# adc.net
KiCad netlist of a schematic drawn in Altium Designer
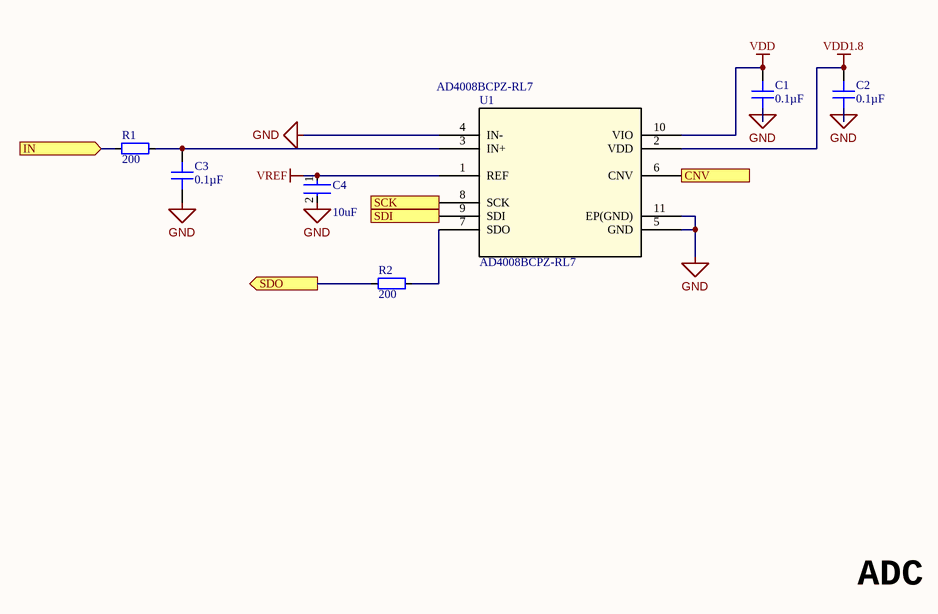
[diagram p0: adc.SchDoc]

(export (version "E")
  (design (tool "Eeschema 10.0.6"))
  (components
    (comp (ref "C1")
      (value "0.1µF")
      (footprint "FP-GRM155-0_05-IPC_B")
      (description "CAP CER 0.1UF 25V X7R 0402")
      (fields (field (name "MANUFACTURER") "AVX Corporation") (field (name "PART NUMBER") "04023C104KAT2A"))
      (libsource (lib "Celestial Altium Library - altium_library") (part "Capacitor"))
    )
    (comp (ref "C2")
      (value "0.1µF")
      (footprint "FP-GRM155-0_05-IPC_B")
      (description "CAP CER 0.1UF 25V X7R 0402")
      (fields (field (name "MANUFACTURER") "AVX Corporation") (field (name "PART NUMBER") "04023C104KAT2A"))
      (libsource (lib "Celestial Altium Library - altium_library") (part "Capacitor"))
    )
    (comp (ref "C3")
      (value "0.1µF")
      (footprint "FP-GRM155-0_05-IPC_B")
      (description "CAP CER 0.1UF 25V X7R 0402")
      (fields (field (name "MANUFACTURER") "AVX Corporation") (field (name "PART NUMBER") "04023C104KAT2A"))
      (libsource (lib "Celestial Altium Library - altium_library") (part "Capacitor"))
    )
    (comp (ref "C4")
      (value "CL21B106KQQNNNG")
      (footprint "FP-CL21-IPC_C")
      (description "CL21 Series 0805 10uF 6.3V ±10% Tolerance X7R Multilayer Ceramic Chip Capacitor")
      (fields
        (field (name "CAPACITANCE") "10uF")
        (field (name "TOLERANCE") "10%")
        (field (name "VOLTAGE") "6.3V")
      )
      (libsource (lib "Altium Content Vault") (part "b4654b650e69147ec39a6b967a45e02"))
    )
    (comp (ref "R1")
      (value "200")
      (footprint "FP-CRCW0402-e3-IPC_B")
      (description "Resistor")
      (fields (field (name "Comment") "Res_0402"))
      (libsource (lib "SCH_Passive") (part "Res_0402"))
    )
    (comp (ref "R2")
      (value "200")
      (footprint "FP-CRCW0402-e3-IPC_B")
      (description "Resistor")
      (fields (field (name "Comment") "Res_0402"))
      (libsource (lib "SCH_Passive") (part "Res_0402"))
    )
    (comp (ref "U1")
      (value "AD4008BCPZ-RL7")
      (footprint "CP_10_9")
      (description "16-Bit, 2 MSPS/1 MSPS/500 kSPS,\r\nPrecision, Pseudo Differential, SAR ADCs")
      (fields (field (name "SUPPLIER PART NUMBER 1") "AD4008BCPZ-RL7"))
      (libsource (lib "dvrk-s-pwm") (part "AD4008BCPZ-RL7"))
    )
  )
  (nets
    (net (code "1") (name "/CNV") (class "Default")
      (node (ref "U1") (pin "6") (pinfunction "CNV_6") (pintype "passive"))
    )
    (net (code "2") (name "/IN") (class "Default")
      (node (ref "R1") (pin "1") (pinfunction "1_1") (pintype "passive"))
    )
    (net (code "3") (name "/SCK") (class "Default")
      (node (ref "U1") (pin "8") (pinfunction "SCK_8") (pintype "passive"))
    )
    (net (code "4") (name "/SDI") (class "Default")
      (node (ref "U1") (pin "9") (pinfunction "SDI_9") (pintype "passive"))
    )
    (net (code "5") (name "/SDO") (class "Default")
      (node (ref "R2") (pin "1") (pinfunction "1_1") (pintype "passive"))
    )
    (net (code "6") (name "GND") (class "Default")
      (node (ref "C1") (pin "2") (pinfunction "2_2") (pintype "passive"))
      (node (ref "C2") (pin "2") (pinfunction "2_2") (pintype "passive"))
      (node (ref "C3") (pin "2") (pinfunction "2_2") (pintype "passive"))
      (node (ref "C4") (pin "2") (pinfunction "2_2") (pintype "passive"))
      (node (ref "U1") (pin "11") (pinfunction "EP(GND)_11") (pintype "passive"))
      (node (ref "U1") (pin "4") (pinfunction "IN-_4") (pintype "passive"))
      (node (ref "U1") (pin "5") (pinfunction "GND_5") (pintype "passive"))
    )
    (net (code "7") (name "Net-(U1-IN+)") (class "Default")
      (node (ref "C3") (pin "1") (pinfunction "1_1") (pintype "passive"))
      (node (ref "R1") (pin "2") (pinfunction "2_2") (pintype "passive"))
      (node (ref "U1") (pin "3") (pinfunction "IN+_3") (pintype "passive"))
    )
    (net (code "8") (name "Net-(U1-SDO)") (class "Default")
      (node (ref "R2") (pin "2") (pinfunction "2_2") (pintype "passive"))
      (node (ref "U1") (pin "7") (pinfunction "SDO_7") (pintype "passive"))
    )
    (net (code "9") (name "VDD") (class "Default")
      (node (ref "C1") (pin "1") (pinfunction "1_1") (pintype "passive"))
      (node (ref "U1") (pin "10") (pinfunction "VIO_10") (pintype "passive"))
    )
    (net (code "10") (name "VDD1.8") (class "Default")
      (node (ref "C2") (pin "1") (pinfunction "1_1") (pintype "passive"))
      (node (ref "U1") (pin "2") (pinfunction "VDD_2") (pintype "passive"))
    )
    (net (code "11") (name "VREF") (class "Default")
      (node (ref "C4") (pin "1") (pinfunction "1_1") (pintype "passive"))
      (node (ref "U1") (pin "1") (pinfunction "REF_1") (pintype "passive"))
    )
  )
)
